# HW2.net
KiCad netlist of a schematic drawn in EAGLE
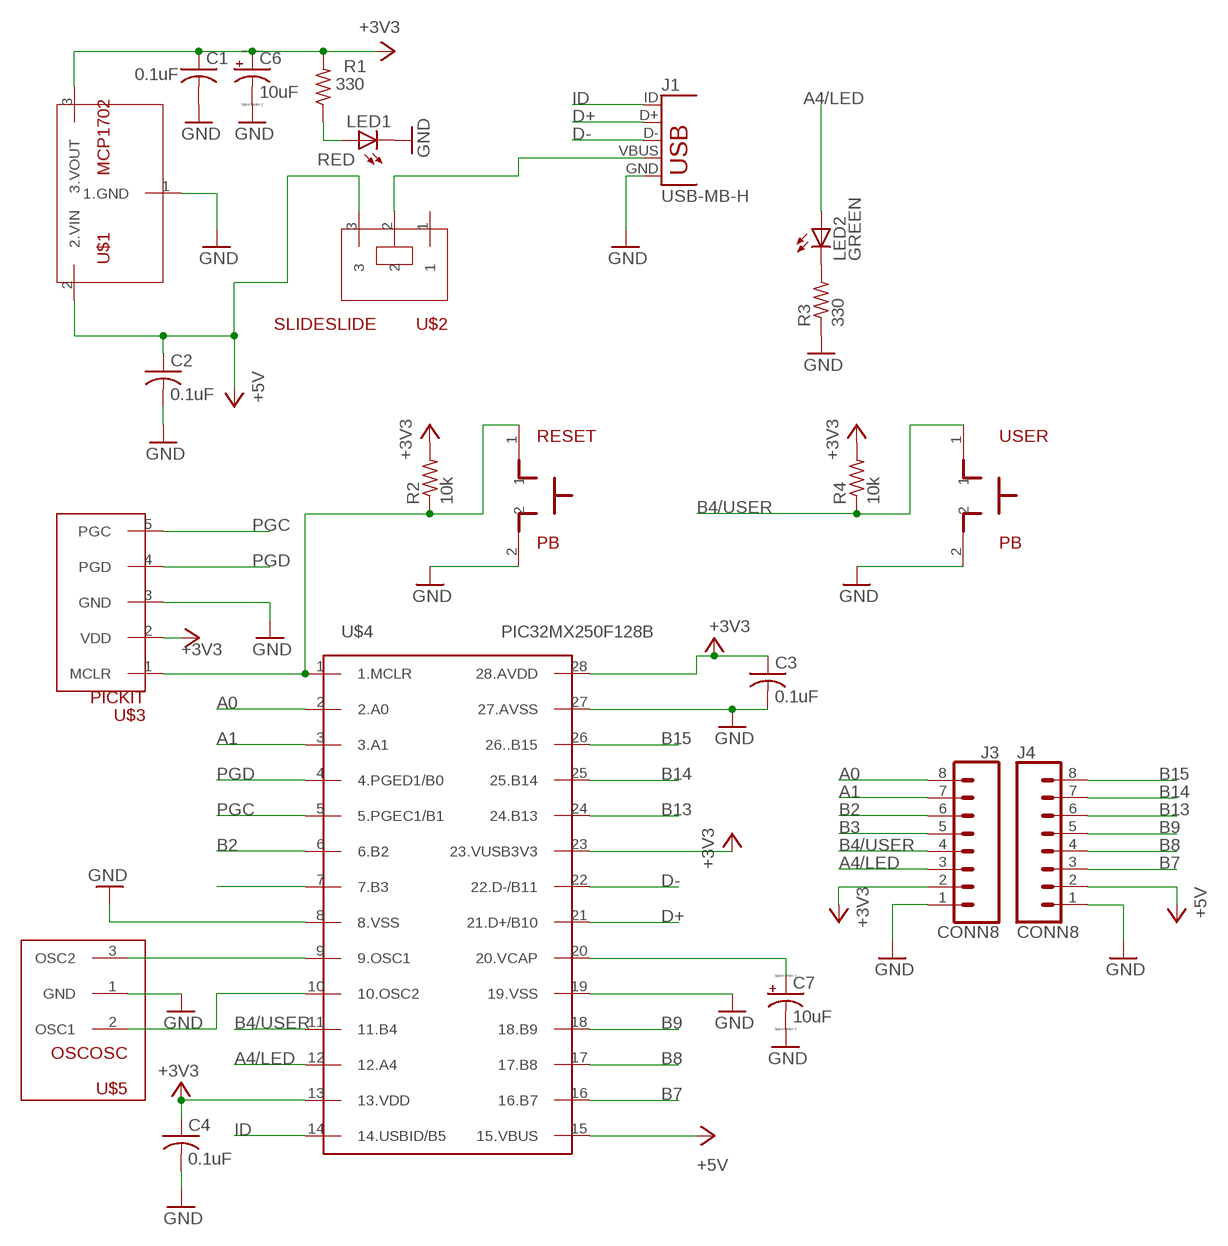
[diagram p0: schematic, sheet 1]

(export (version "E")
  (design (tool "Eeschema 10.0.6"))
  (components
    (comp (ref "C1")
      (value "0.1uF")
      (footprint "eagle-import:C025-025X050")
      (libsource (lib "eagle-import") (part "C-US025-025X050"))
    )
    (comp (ref "C2")
      (value "0.1uF")
      (footprint "eagle-import:C025-025X050")
      (libsource (lib "eagle-import") (part "C-US025-025X050"))
    )
    (comp (ref "C3")
      (value "0.1uF")
      (footprint "eagle-import:C025-025X050")
      (libsource (lib "eagle-import") (part "C-US025-025X050"))
    )
    (comp (ref "C4")
      (value "0.1uF")
      (footprint "eagle-import:C025-025X050")
      (libsource (lib "eagle-import") (part "C-US025-025X050"))
    )
    (comp (ref "C6")
      (value "10uF")
      (footprint "eagle-import:B45181B")
      (libsource (lib "eagle-import") (part "CPOL-USB45181B"))
    )
    (comp (ref "C7")
      (value "10uF")
      (footprint "eagle-import:B45181B")
      (libsource (lib "eagle-import") (part "CPOL-USB45181B"))
    )
    (comp (ref "J1")
      (value "USB-MB-H")
      (footprint "eagle-import:USB-MB-H")
      (libsource (lib "eagle-import") (part "USB-MB-H"))
    )
    (comp (ref "J3")
      (value "CONN8")
      (footprint "eagle-import:1X08")
      (libsource (lib "eagle-import") (part "CONN8"))
    )
    (comp (ref "J4")
      (value "CONN8")
      (footprint "eagle-import:1X08")
      (libsource (lib "eagle-import") (part "CONN8"))
    )
    (comp (ref "LED1")
      (value "RED")
      (footprint "eagle-import:LED3MM")
      (libsource (lib "eagle-import") (part "LED3MM"))
    )
    (comp (ref "LED2")
      (value "GREEN")
      (footprint "eagle-import:LED3MM")
      (libsource (lib "eagle-import") (part "LED3MM"))
    )
    (comp (ref "R1")
      (value "330")
      (footprint "eagle-import:0207_10")
      (libsource (lib "eagle-import") (part "R-US_0207/10"))
    )
    (comp (ref "R2")
      (value "10k")
      (footprint "eagle-import:0207_10")
      (libsource (lib "eagle-import") (part "R-US_0207/10"))
    )
    (comp (ref "R3")
      (value "330")
      (footprint "eagle-import:0207_10")
      (libsource (lib "eagle-import") (part "R-US_0207/10"))
    )
    (comp (ref "R4")
      (value "10k")
      (footprint "eagle-import:0207_10")
      (libsource (lib "eagle-import") (part "R-US_0207/10"))
    )
    (comp (ref "RESET")
      (value "PB")
      (footprint "eagle-import:PB")
      (libsource (lib "eagle-import") (part "PB"))
    )
    (comp (ref "U$1")
      (value "MCP1702")
      (footprint "eagle-import:TO92")
      (libsource (lib "eagle-import") (part "MCP1702"))
    )
    (comp (ref "U$2")
      (value "SLIDESLIDE")
      (footprint "eagle-import:SLIDE")
      (libsource (lib "eagle-import") (part "SLIDESLIDE"))
    )
    (comp (ref "U$3")
      (value "PICKIT")
      (footprint "eagle-import:1X05")
      (libsource (lib "eagle-import") (part "PICKIT"))
    )
    (comp (ref "U$4")
      (value "PIC32MX250F128B")
      (footprint "eagle-import:DIL28-3")
      (libsource (lib "eagle-import") (part "PIC32MX250F128B"))
    )
    (comp (ref "U$5")
      (value "OSCOSC")
      (footprint "eagle-import:OSC")
      (libsource (lib "eagle-import") (part "OSCOSC"))
    )
    (comp (ref "USER")
      (value "PB")
      (footprint "eagle-import:PB")
      (libsource (lib "eagle-import") (part "PB"))
    )
  )
  (nets
    (net (code "1") (name "+3V3") (class "Default")
      (node (ref "C1") (pin "1") (pinfunction "1_1") (pintype "passive"))
      (node (ref "C3") (pin "1") (pinfunction "1_1") (pintype "passive"))
      (node (ref "C4") (pin "1") (pinfunction "1_1") (pintype "passive"))
      (node (ref "C6") (pin "+") (pinfunction "+_+") (pintype "passive"))
      (node (ref "J3") (pin "2") (pinfunction "2_2") (pintype "passive"))
      (node (ref "R1") (pin "2") (pinfunction "2_2") (pintype "passive"))
      (node (ref "R2") (pin "2") (pinfunction "2_2") (pintype "passive"))
      (node (ref "R4") (pin "2") (pinfunction "2_2") (pintype "passive"))
      (node (ref "U$1") (pin "3") (pinfunction "3.VOUT_3") (pintype "bidirectional"))
      (node (ref "U$3") (pin "2") (pinfunction "VDD_2") (pintype "bidirectional"))
      (node (ref "U$4") (pin "13") (pinfunction "13.VDD_13") (pintype "bidirectional"))
      (node (ref "U$4") (pin "23") (pinfunction "23.VUSB3V3_23") (pintype "bidirectional"))
      (node (ref "U$4") (pin "28") (pinfunction "28.AVDD_28") (pintype "bidirectional"))
    )
    (net (code "2") (name "+5V") (class "Default")
      (node (ref "C2") (pin "1") (pinfunction "1_1") (pintype "passive"))
      (node (ref "J4") (pin "2") (pinfunction "2_2") (pintype "passive"))
      (node (ref "U$1") (pin "2") (pinfunction "2.VIN_2") (pintype "bidirectional"))
      (node (ref "U$2") (pin "3") (pinfunction "3_3") (pintype "bidirectional"))
      (node (ref "U$4") (pin "15") (pinfunction "15.VBUS_15") (pintype "bidirectional"))
    )
    (net (code "3") (name "/A0") (class "Default")
      (node (ref "J3") (pin "8") (pinfunction "8_8") (pintype "passive"))
      (node (ref "U$4") (pin "2") (pinfunction "2.A0_2") (pintype "bidirectional"))
    )
    (net (code "4") (name "/A1") (class "Default")
      (node (ref "J3") (pin "7") (pinfunction "7_7") (pintype "passive"))
      (node (ref "U$4") (pin "3") (pinfunction "3.A1_3") (pintype "bidirectional"))
    )
    (net (code "5") (name "/A4{slash}LED") (class "Default")
      (node (ref "J3") (pin "3") (pinfunction "3_3") (pintype "passive"))
      (node (ref "LED2") (pin "A") (pinfunction "A_A") (pintype "passive"))
      (node (ref "U$4") (pin "12") (pinfunction "12.A4_12") (pintype "bidirectional"))
    )
    (net (code "6") (name "/B2") (class "Default")
      (node (ref "J3") (pin "6") (pinfunction "6_6") (pintype "passive"))
      (node (ref "U$4") (pin "6") (pinfunction "6.B2_6") (pintype "bidirectional"))
    )
    (net (code "7") (name "/B3") (class "Default")
      (node (ref "J3") (pin "5") (pinfunction "5_5") (pintype "passive"))
      (node (ref "U$4") (pin "7") (pinfunction "7.B3_7") (pintype "bidirectional"))
    )
    (net (code "8") (name "/B4{slash}USER") (class "Default")
      (node (ref "J3") (pin "4") (pinfunction "4_4") (pintype "passive"))
      (node (ref "R4") (pin "1") (pinfunction "1_1") (pintype "passive"))
      (node (ref "U$4") (pin "11") (pinfunction "11.B4_11") (pintype "bidirectional"))
      (node (ref "USER") (pin "1") (pinfunction "1_1") (pintype "bidirectional"))
    )
    (net (code "9") (name "/B7") (class "Default")
      (node (ref "J4") (pin "3") (pinfunction "3_3") (pintype "passive"))
      (node (ref "U$4") (pin "16") (pinfunction "16.B7_16") (pintype "bidirectional"))
    )
    (net (code "10") (name "/B8") (class "Default")
      (node (ref "J4") (pin "4") (pinfunction "4_4") (pintype "passive"))
      (node (ref "U$4") (pin "17") (pinfunction "17.B8_17") (pintype "bidirectional"))
    )
    (net (code "11") (name "/B9") (class "Default")
      (node (ref "J4") (pin "5") (pinfunction "5_5") (pintype "passive"))
      (node (ref "U$4") (pin "18") (pinfunction "18.B9_18") (pintype "bidirectional"))
    )
    (net (code "12") (name "/B13") (class "Default")
      (node (ref "J4") (pin "6") (pinfunction "6_6") (pintype "passive"))
      (node (ref "U$4") (pin "24") (pinfunction "24.B13_24") (pintype "bidirectional"))
    )
    (net (code "13") (name "/B14") (class "Default")
      (node (ref "J4") (pin "7") (pinfunction "7_7") (pintype "passive"))
      (node (ref "U$4") (pin "25") (pinfunction "25.B14_25") (pintype "bidirectional"))
    )
    (net (code "14") (name "/B15") (class "Default")
      (node (ref "J4") (pin "8") (pinfunction "8_8") (pintype "passive"))
      (node (ref "U$4") (pin "26") (pinfunction "26..B15_26") (pintype "bidirectional"))
    )
    (net (code "15") (name "/D+") (class "Default")
      (node (ref "J1") (pin "D+") (pinfunction "D+_D+") (pintype "bidirectional"))
      (node (ref "U$4") (pin "21") (pinfunction "21.D+/B10_21") (pintype "bidirectional"))
    )
    (net (code "16") (name "/D-") (class "Default")
      (node (ref "J1") (pin "D-") (pinfunction "D-_D-") (pintype "bidirectional"))
      (node (ref "U$4") (pin "22") (pinfunction "22.D-/B11_22") (pintype "bidirectional"))
    )
    (net (code "17") (name "/ID") (class "Default")
      (node (ref "J1") (pin "ID") (pinfunction "ID_ID") (pintype "bidirectional"))
      (node (ref "U$4") (pin "14") (pinfunction "14.USBID/B5_14") (pintype "bidirectional"))
    )
    (net (code "18") (name "/PGC") (class "Default")
      (node (ref "U$3") (pin "5") (pinfunction "PGC_5") (pintype "bidirectional"))
      (node (ref "U$4") (pin "5") (pinfunction "5.PGEC1/B1_5") (pintype "bidirectional"))
    )
    (net (code "19") (name "/PGD") (class "Default")
      (node (ref "U$3") (pin "4") (pinfunction "PGD_4") (pintype "bidirectional"))
      (node (ref "U$4") (pin "4") (pinfunction "4.PGED1/B0_4") (pintype "bidirectional"))
    )
    (net (code "20") (name "GND") (class "Default")
      (node (ref "C1") (pin "2") (pinfunction "2_2") (pintype "passive"))
      (node (ref "C2") (pin "2") (pinfunction "2_2") (pintype "passive"))
      (node (ref "C3") (pin "2") (pinfunction "2_2") (pintype "passive"))
      (node (ref "C4") (pin "2") (pinfunction "2_2") (pintype "passive"))
      (node (ref "C6") (pin "-") (pinfunction "-_-") (pintype "passive"))
      (node (ref "C7") (pin "-") (pinfunction "-_-") (pintype "passive"))
      (node (ref "J1") (pin "GND") (pinfunction "GND_GND") (pintype "bidirectional"))
      (node (ref "J3") (pin "1") (pinfunction "1_1") (pintype "passive"))
      (node (ref "J4") (pin "1") (pinfunction "1_1") (pintype "passive"))
      (node (ref "LED1") (pin "K") (pinfunction "C_K") (pintype "passive"))
      (node (ref "R3") (pin "1") (pinfunction "1_1") (pintype "passive"))
      (node (ref "RESET") (pin "2") (pinfunction "2_2") (pintype "bidirectional"))
      (node (ref "U$1") (pin "1") (pinfunction "1.GND_1") (pintype "bidirectional"))
      (node (ref "U$3") (pin "3") (pinfunction "GND_3") (pintype "bidirectional"))
      (node (ref "U$4") (pin "19") (pinfunction "19.VSS_19") (pintype "bidirectional"))
      (node (ref "U$4") (pin "27") (pinfunction "27.AVSS_27") (pintype "bidirectional"))
      (node (ref "U$4") (pin "8") (pinfunction "8.VSS_8") (pintype "bidirectional"))
      (node (ref "U$5") (pin "1") (pinfunction "GND_1") (pintype "bidirectional"))
      (node (ref "USER") (pin "2") (pinfunction "2_2") (pintype "bidirectional"))
    )
    (net (code "21") (name "Net-(J1-PadVBUS)") (class "Default")
      (node (ref "J1") (pin "VBUS") (pinfunction "VBUS_VBUS") (pintype "bidirectional"))
      (node (ref "U$2") (pin "2") (pinfunction "2_2") (pintype "bidirectional"))
    )
    (net (code "22") (name "Net-(LED1-PadA)") (class "Default")
      (node (ref "LED1") (pin "A") (pinfunction "A_A") (pintype "passive"))
      (node (ref "R1") (pin "1") (pinfunction "1_1") (pintype "passive"))
    )
    (net (code "23") (name "Net-(LED2-C)") (class "Default")
      (node (ref "LED2") (pin "K") (pinfunction "C_K") (pintype "passive"))
      (node (ref "R3") (pin "2") (pinfunction "2_2") (pintype "passive"))
    )
    (net (code "24") (name "Net-(U$3-MCLR)") (class "Default")
      (node (ref "R2") (pin "1") (pinfunction "1_1") (pintype "passive"))
      (node (ref "RESET") (pin "1") (pinfunction "1_1") (pintype "bidirectional"))
      (node (ref "U$3") (pin "1") (pinfunction "MCLR_1") (pintype "bidirectional"))
      (node (ref "U$4") (pin "1") (pinfunction "1.MCLR_1") (pintype "bidirectional"))
    )
    (net (code "25") (name "Net-(U$4-9.OSC1)") (class "Default")
      (node (ref "U$4") (pin "9") (pinfunction "9.OSC1_9") (pintype "bidirectional"))
      (node (ref "U$5") (pin "3") (pinfunction "OSC2_3") (pintype "bidirectional"))
    )
    (net (code "26") (name "Net-(U$4-10.OSC2)") (class "Default")
      (node (ref "U$4") (pin "10") (pinfunction "10.OSC2_10") (pintype "bidirectional"))
      (node (ref "U$5") (pin "2") (pinfunction "OSC1_2") (pintype "bidirectional"))
    )
    (net (code "27") (name "Net-(U$4-20.VCAP)") (class "Default")
      (node (ref "C7") (pin "+") (pinfunction "+_+") (pintype "passive"))
      (node (ref "U$4") (pin "20") (pinfunction "20.VCAP_20") (pintype "bidirectional"))
    )
    (net (code "28") (name "unconnected-(U$2-Pad1)") (class "Default")
      (node (ref "U$2") (pin "1") (pinfunction "1_1") (pintype "bidirectional"))
    )
  )
)
